# HDMI_To_MIPI.net
KiCad netlist of a schematic drawn in Altium Designer
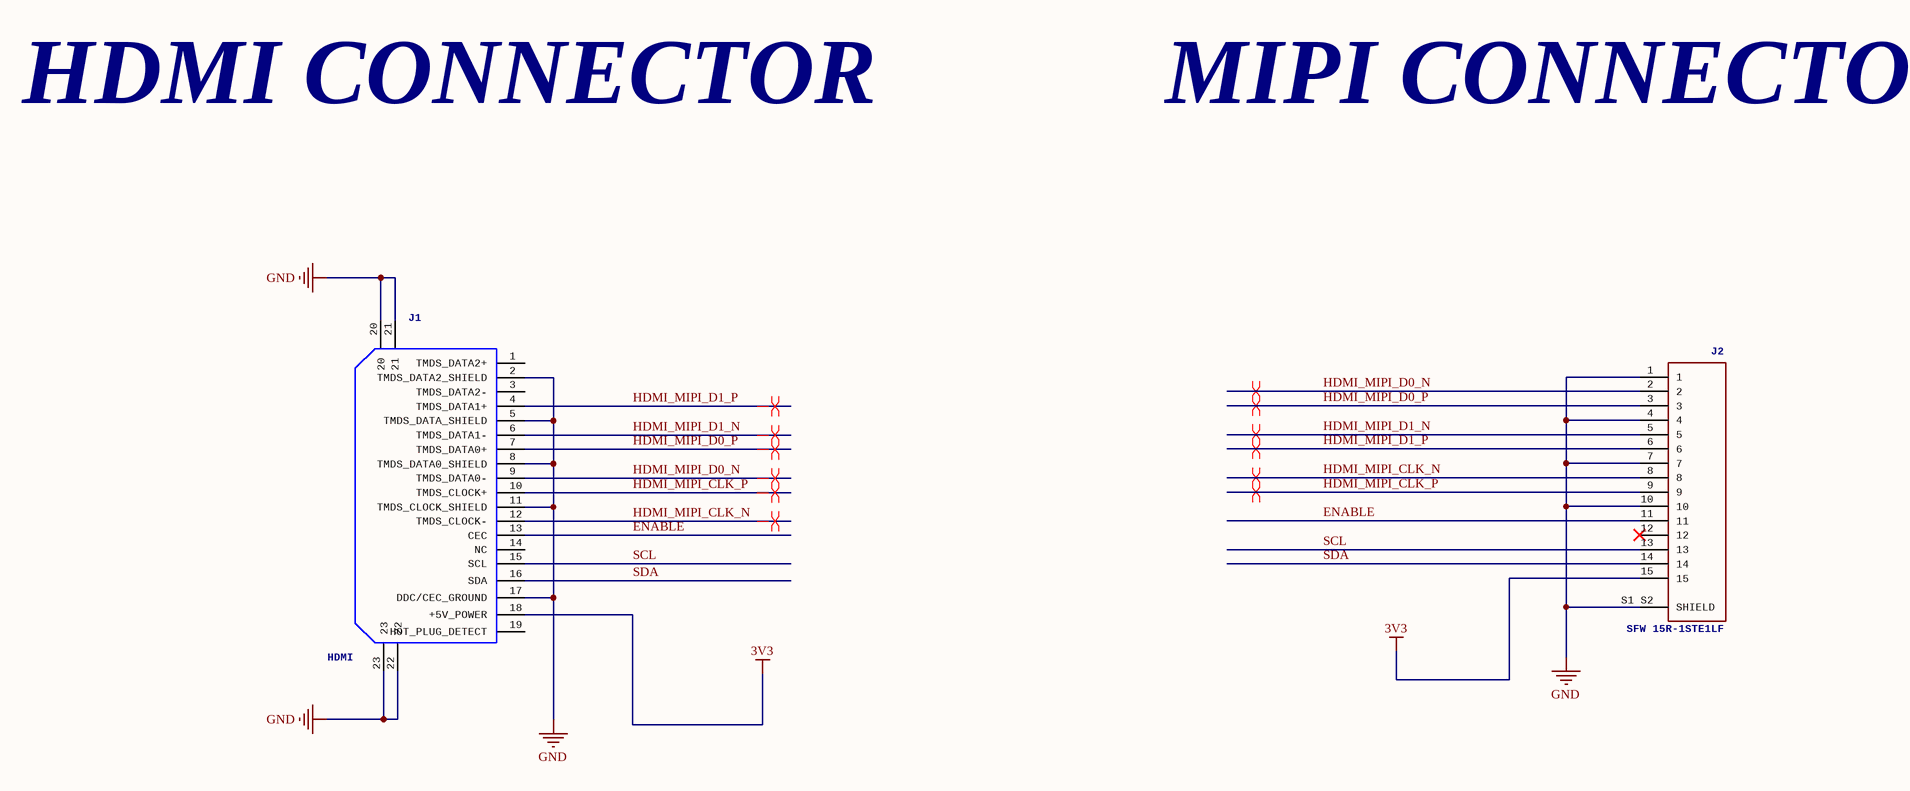
[diagram p0: HDMI_To_MIPI.SchDoc]

(export (version "E")
  (design (tool "Eeschema 10.0.6"))
  (components
    (comp (ref "J1")
      (value "HDMI")
      (footprint "2000124100BK")
      (fields (field (name "MANUFACTURER_PART_NUMBER") "2000-1-2-41-00-BK"))
      (libsource (lib "TASK-3DLIB") (part "HDMI-normal"))
    )
    (comp (ref "J2")
      (value "SFW 15R-1STE1LF")
      (footprint "AMPHENOL_SFW15R-1STE1LF")
      (fields
        (field (name "DIGI-KEY_PART_NUMBER") "609-1905-1-ND")
        (field (name "MF") "Amphenol ICC")
        (field (name "MP") "SFW15R-1STE1LF")
      )
      (libsource (lib "TASK-3DLIB") (part "HEADER15"))
    )
  )
  (nets
    (net (code "1") (name "/ENABLE") (class "Default")
      (node (ref "J1") (pin "13") (pinfunction "CEC_13") (pintype "passive"))
      (node (ref "J2") (pin "11") (pinfunction "11_11") (pintype "passive"))
    )
    (net (code "2") (name "/HDMI_MIPI_CLK_N") (class "Default")
      (node (ref "J1") (pin "12") (pinfunction "TMDS_CLOCK-_12") (pintype "passive"))
      (node (ref "J2") (pin "8") (pinfunction "8_8") (pintype "passive"))
    )
    (net (code "3") (name "/HDMI_MIPI_CLK_P") (class "Default")
      (node (ref "J1") (pin "10") (pinfunction "TMDS_CLOCK+_10") (pintype "passive"))
      (node (ref "J2") (pin "9") (pinfunction "9_9") (pintype "passive"))
    )
    (net (code "4") (name "/HDMI_MIPI_D0_N") (class "Default")
      (node (ref "J1") (pin "9") (pinfunction "TMDS_DATA0-_9") (pintype "passive"))
      (node (ref "J2") (pin "2") (pinfunction "2_2") (pintype "passive"))
    )
    (net (code "5") (name "/HDMI_MIPI_D0_P") (class "Default")
      (node (ref "J1") (pin "7") (pinfunction "TMDS_DATA0+_7") (pintype "passive"))
      (node (ref "J2") (pin "3") (pinfunction "3_3") (pintype "passive"))
    )
    (net (code "6") (name "/HDMI_MIPI_D1_N") (class "Default")
      (node (ref "J1") (pin "6") (pinfunction "TMDS_DATA1-_6") (pintype "passive"))
      (node (ref "J2") (pin "5") (pinfunction "5_5") (pintype "passive"))
    )
    (net (code "7") (name "/HDMI_MIPI_D1_P") (class "Default")
      (node (ref "J1") (pin "4") (pinfunction "TMDS_DATA1+_4") (pintype "passive"))
      (node (ref "J2") (pin "6") (pinfunction "6_6") (pintype "passive"))
    )
    (net (code "8") (name "/SCL") (class "Default")
      (node (ref "J1") (pin "15") (pinfunction "SCL_15") (pintype "passive"))
      (node (ref "J2") (pin "13") (pinfunction "13_13") (pintype "passive"))
    )
    (net (code "9") (name "/SDA") (class "Default")
      (node (ref "J1") (pin "16") (pinfunction "SDA_16") (pintype "passive"))
      (node (ref "J2") (pin "14") (pinfunction "14_14") (pintype "passive"))
    )
    (net (code "10") (name "3V3") (class "Default")
      (node (ref "J1") (pin "18") (pinfunction "+5V_POWER_18") (pintype "passive"))
      (node (ref "J2") (pin "15") (pinfunction "15_15") (pintype "passive"))
    )
    (net (code "11") (name "GND") (class "Default")
      (node (ref "J1") (pin "11") (pinfunction "TMDS_CLOCK_SHIELD_11") (pintype "passive"))
      (node (ref "J1") (pin "17") (pinfunction "DDC/CEC_GROUND_17") (pintype "passive"))
      (node (ref "J1") (pin "2") (pinfunction "TMDS_DATA2_SHIELD_2") (pintype "passive"))
      (node (ref "J1") (pin "20") (pinfunction "20_20") (pintype "passive"))
      (node (ref "J1") (pin "21") (pinfunction "21_21") (pintype "passive"))
      (node (ref "J1") (pin "22") (pinfunction "22_22") (pintype "passive"))
      (node (ref "J1") (pin "23") (pinfunction "23_23") (pintype "passive"))
      (node (ref "J1") (pin "5") (pinfunction "TMDS_DATA_SHIELD_5") (pintype "passive"))
      (node (ref "J1") (pin "8") (pinfunction "TMDS_DATA0_SHIELD_8") (pintype "passive"))
      (node (ref "J2") (pin "1") (pinfunction "1_1") (pintype "passive"))
      (node (ref "J2") (pin "10") (pinfunction "10_10") (pintype "passive"))
      (node (ref "J2") (pin "4") (pinfunction "4_4") (pintype "passive"))
      (node (ref "J2") (pin "7") (pinfunction "7_7") (pintype "passive"))
      (node (ref "J2") (pin "S1_S2") (pinfunction "SHIELD_S1_S2") (pintype "passive"))
    )
    (net (code "12") (name "unconnected-(J1-HOT_PLUG_DETECT-Pad19)") (class "Default")
      (node (ref "J1") (pin "19") (pinfunction "HOT_PLUG_DETECT_19") (pintype "passive"))
    )
    (net (code "13") (name "unconnected-(J1-NC-Pad14)") (class "Default")
      (node (ref "J1") (pin "14") (pinfunction "NC_14") (pintype "passive"))
    )
    (net (code "14") (name "unconnected-(J1-TMDS_DATA2+-Pad1)") (class "Default")
      (node (ref "J1") (pin "1") (pinfunction "TMDS_DATA2+_1") (pintype "passive"))
    )
    (net (code "15") (name "unconnected-(J1-TMDS_DATA2--Pad3)") (class "Default")
      (node (ref "J1") (pin "3") (pinfunction "TMDS_DATA2-_3") (pintype "passive"))
    )
    (net (code "16") (name "unconnected-(J2-Pad12)") (class "Default")
      (node (ref "J2") (pin "12") (pinfunction "12_12") (pintype "passive+no_connect"))
    )
  )
)
